# S7_RF.net
KiCad netlist of a schematic drawn in Altium Designer
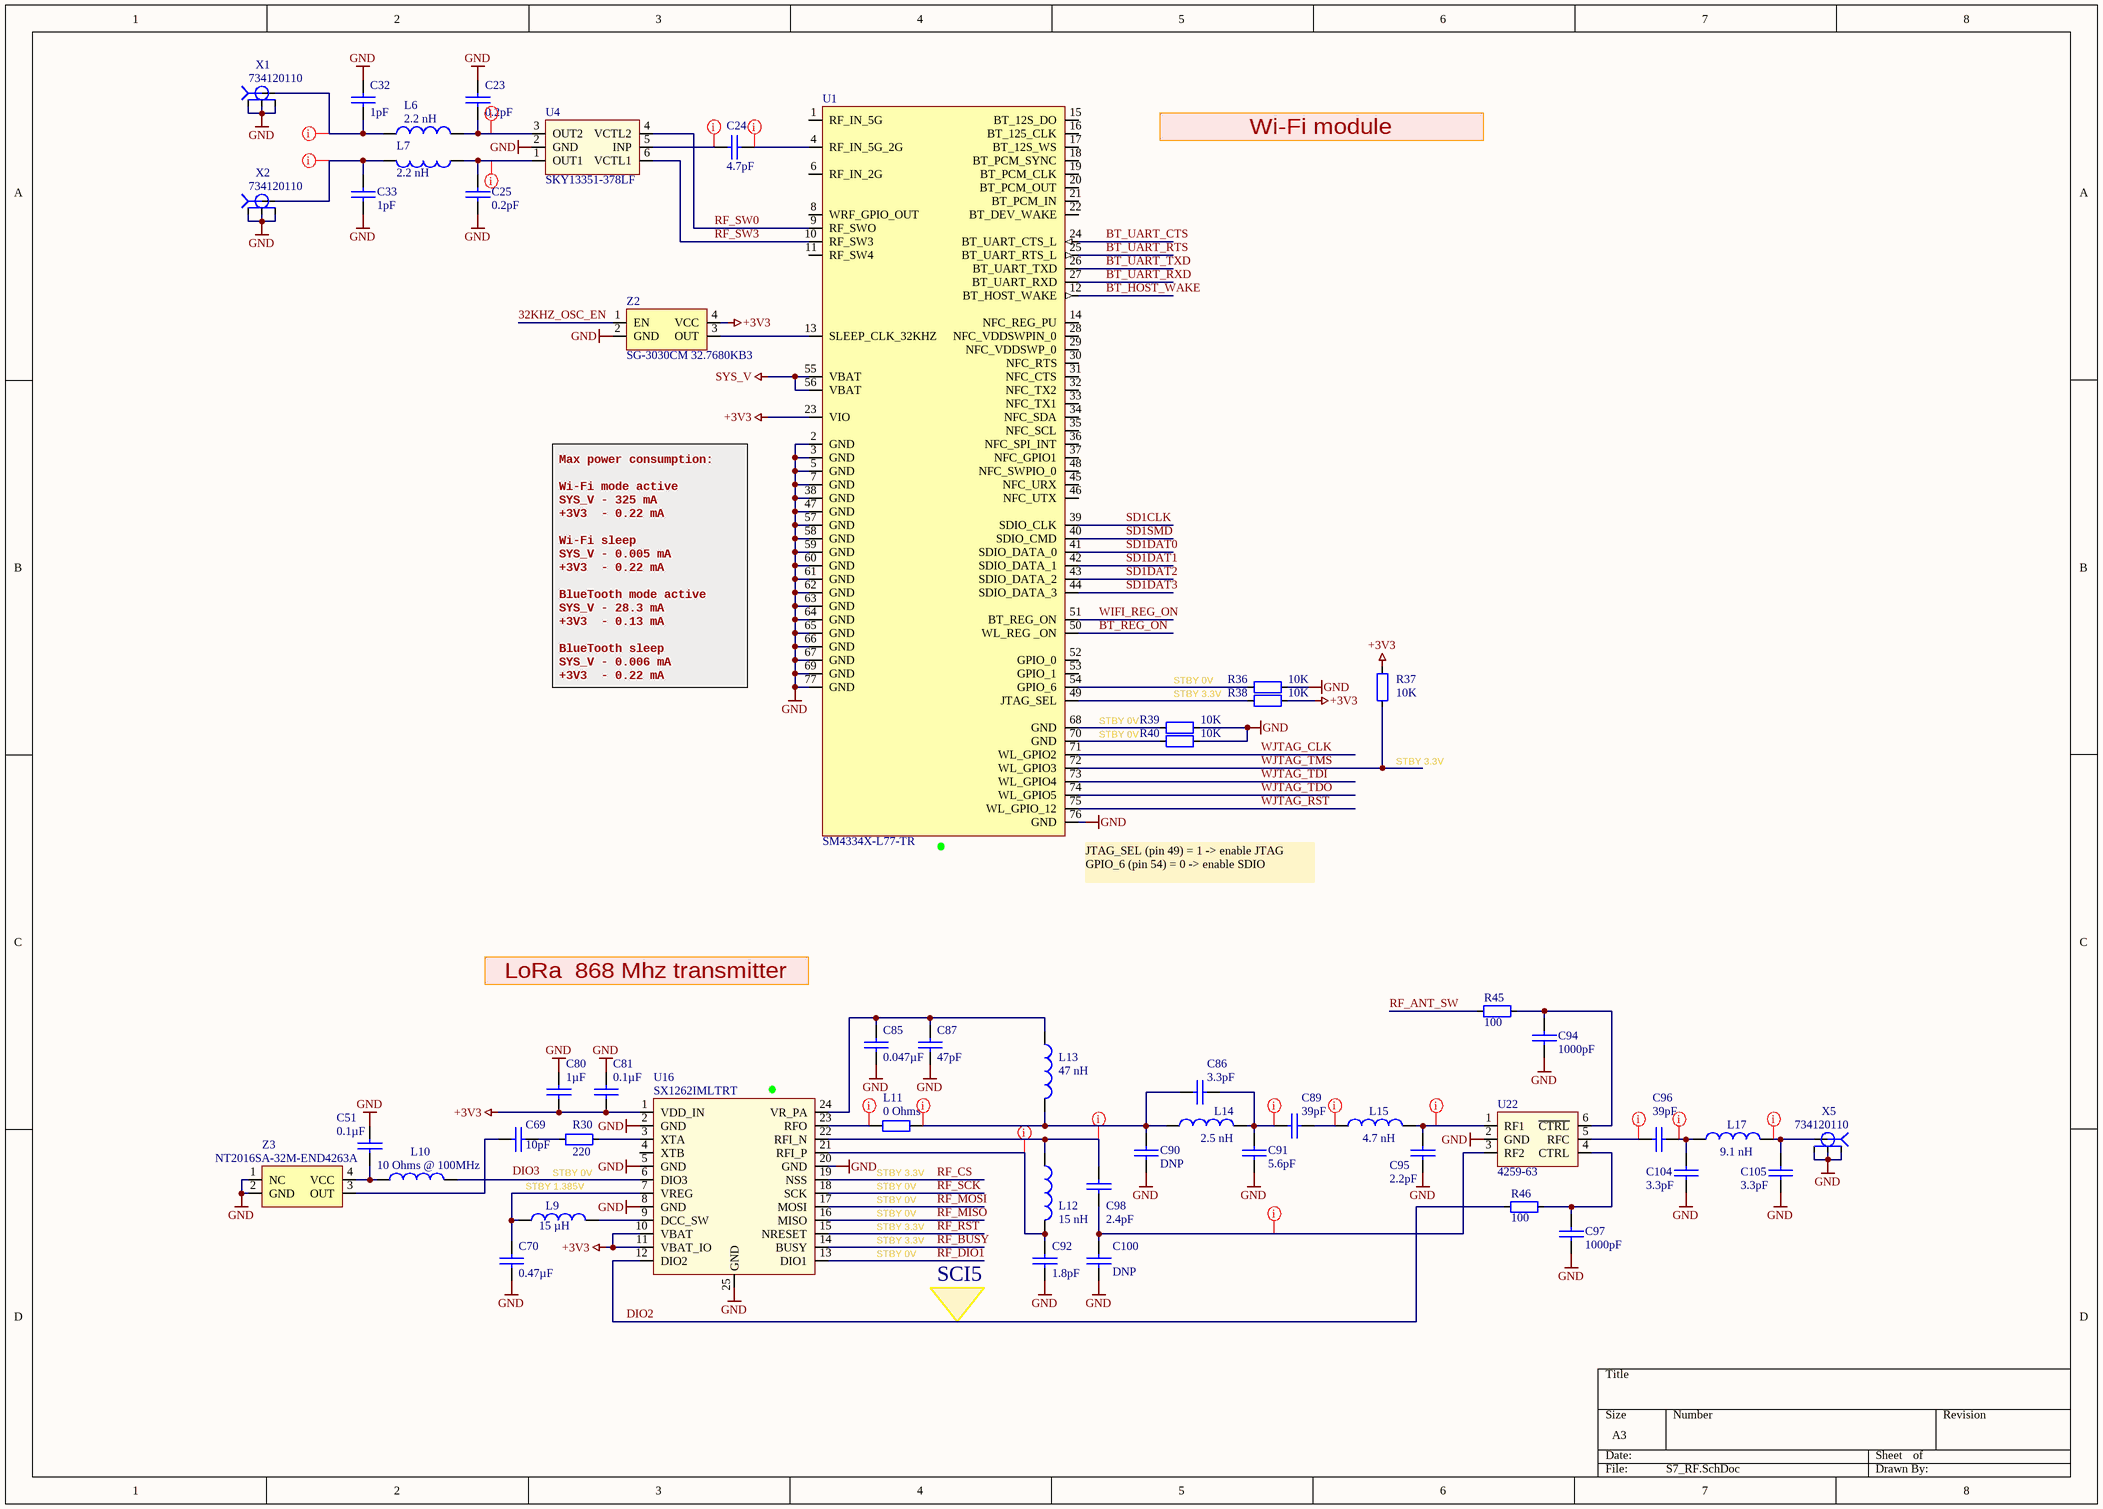
[diagram p0: S7_RF.SchDoc]

(export (version "E")
  (design (tool "Eeschema 10.0.6"))
  (components
    (comp (ref "C23")
      (value "0.2pF")
      (footprint "0402 CAP")
      (fields
        (field (name "PART NUMBER") "500R07S0R2BV4T")
        (field (name "MANUFACTURER") "Johanson Technology Inc.")
        (field (name "PARTNUM") "712-1160-1-ND")
      )
      (libsource (lib "ea_PassivComps") (part "Capacitor"))
    )
    (comp (ref "C24")
      (value "4.7pF")
      (footprint "0402 CAP")
      (fields
        (field (name "PART NUMBER") "500R07S4R7CV4T")
        (field (name "MANUFACTURER") "Johanson Technology Inc.")
        (field (name "PARTNUM") "712-1287-1-ND")
      )
      (libsource (lib "ea_PassivComps") (part "Capacitor"))
    )
    (comp (ref "C25")
      (value "0.2pF")
      (footprint "0402 CAP")
      (fields
        (field (name "PART NUMBER") "500R07S0R2BV4T")
        (field (name "MANUFACTURER") "Johanson Technology Inc.")
        (field (name "PARTNUM") "712-1160-1-ND")
      )
      (libsource (lib "ea_PassivComps") (part "Capacitor"))
    )
    (comp (ref "C32")
      (value "1pF")
      (footprint "0402 CAP")
      (fields
        (field (name "PART NUMBER") "GJM1555C1H1R0CB01D")
        (field (name "MANUFACTURER") "Murata Electronics North America")
        (field (name "PARTNUM") "490-3083-1-ND")
      )
      (libsource (lib "ea_PassivComps") (part "Capacitor"))
    )
    (comp (ref "C33")
      (value "1pF")
      (footprint "0402 CAP")
      (fields
        (field (name "PART NUMBER") "GJM1555C1H1R0CB01D")
        (field (name "MANUFACTURER") "Murata Electronics North America")
        (field (name "PARTNUM") "490-3083-1-ND")
      )
      (libsource (lib "ea_PassivComps") (part "Capacitor"))
    )
    (comp (ref "C51")
      (value "0.1µF")
      (footprint "0402 CAP")
      (description "0.1µF, ±10%, 50V, X7R, 0402 (1005 Metric), -55°C ~ 125°C, -, General Purpose")
      (fields
        (field (name "PART NUMBER") "0402B104K500CT")
        (field (name "MANUFACTURER") "Walsin Technology Corporation")
      )
      (libsource (lib "ea_PassivComps") (part "Capacitor"))
    )
    (comp (ref "C69")
      (value "10pF")
      (footprint "0402 CAP")
      (fields
        (field (name "PART NUMBER") "GJM1555C1H100FB01D")
        (field (name "MANUFACTURER") "Murata Electronics North America")
        (field (name "PARTNUM") "490-11189-1-ND")
      )
      (libsource (lib "ea_PassivComps") (part "Capacitor"))
    )
    (comp (ref "C70")
      (value "0.47µF")
      (footprint "0402 CAP")
      (description "0.47µF, ±20%, 25V, X5R, 0402 (1005 Metric), -55°C ~ 85°C, -, Automotive")
      (fields
        (field (name "PART NUMBER") "GRT155R61E474ME01D")
        (field (name "MANUFACTURER") "Murata Electronics North America")
      )
      (libsource (lib "ea_PassivComps") (part "Capacitor"))
    )
    (comp (ref "C80")
      (value "1µF")
      (footprint "0402 CAP")
      (description "1µF, ±20%, 25V, X5R, 0402 (1005 Metric), -55°C ~ 85°C, -, General Purpose")
      (fields (field (name "PART NUMBER") "TMK105BJ105MV-F") (field (name "MANUFACTURER") "Taiyo Yuden"))
      (libsource (lib "ea_PassivComps") (part "Capacitor"))
    )
    (comp (ref "C81")
      (value "0.1µF")
      (footprint "0402 CAP")
      (description "0.1µF, ±10%, 50V, X7R, 0402 (1005 Metric), -55°C ~ 125°C, -, General Purpose")
      (fields
        (field (name "PART NUMBER") "0402B104K500CT")
        (field (name "MANUFACTURER") "Walsin Technology Corporation")
      )
      (libsource (lib "ea_PassivComps") (part "Capacitor"))
    )
    (comp (ref "C85")
      (value "0.047µF")
      (footprint "0402 CAP")
      (description "0.047µF, ±10%, 25V, X7R, 0402 (1005 Metric), -55°C ~ 125°C, -, General Purpose")
      (fields (field (name "PART NUMBER") "CC0402KRX7R8BB473") (field (name "MANUFACTURER") "Yageo"))
      (libsource (lib "ea_PassivComps") (part "Capacitor"))
    )
    (comp (ref "C86")
      (value "3.3pF")
      (footprint "0402 CAP")
      (description "3.3pF, ±0.1pF, 50V, C0G, NP0, 0402 (1005 Metric), -55°C ~ 125°C, -, RF, Microwave, High Frequency")
      (fields
        (field (name "PART NUMBER") "885392005011")
        (field (name "MANUFACTURER") "Wurth Electronics Inc.")
      )
      (libsource (lib "ea_PassivComps") (part "Capacitor"))
    )
    (comp (ref "C87")
      (value "47pF")
      (footprint "0402 CAP")
      (fields
        (field (name "PART NUMBER") "GJM1555C1H470FB01D")
        (field (name "MANUFACTURER") "Murata Electronics North America")
        (field (name "PARTNUM") "490-16376-1-ND")
      )
      (libsource (lib "ea_PassivComps") (part "Capacitor"))
    )
    (comp (ref "C89")
      (value "39pF")
      (footprint "0402 CAP")
      (fields
        (field (name "PART NUMBER") "GJM1555C1H390JB01D")
        (field (name "MANUFACTURER") "Murata Electronics North America")
        (field (name "PARTNUM") "490-17673-1-ND")
      )
      (libsource (lib "ea_PassivComps") (part "Capacitor"))
    )
    (comp (ref "C90")
      (value "DNP")
      (footprint "0402 CAP")
      (fields (field (name "Comment") "Capacitor_0402"))
      (libsource (lib "ea_Capacitors") (part "Capacitor_0402"))
    )
    (comp (ref "C91")
      (value "5.6pF")
      (footprint "0402 CAP")
      (fields
        (field (name "PART NUMBER") "GJM1555C1H5R6BB01D")
        (field (name "MANUFACTURER") "Murata Electronics North America")
        (field (name "PARTNUM") "490-11225-1-ND")
      )
      (libsource (lib "ea_PassivComps") (part "Capacitor"))
    )
    (comp (ref "C92")
      (value "1.8pF")
      (footprint "0402 CAP")
      (fields
        (field (name "PART NUMBER") "GJM1555C1H1R8BB01D")
        (field (name "MANUFACTURER") "Murata Electronics North America")
        (field (name "PARTNUM") "490-8089-1-ND")
      )
      (libsource (lib "ea_PassivComps") (part "Capacitor"))
    )
    (comp (ref "C94")
      (value "1000pF")
      (footprint "0402 CAP")
      (description "1000pF, ±5%, 50V, CH, 0402 (1005 Metric), -25°C ~ 85°C, Low ESL, General Purpose")
      (fields
        (field (name "PART NUMBER") "C1005CH1H102J050BA")
        (field (name "MANUFACTURER") "TDK Corporation")
      )
      (libsource (lib "ea_PassivComps") (part "Capacitor"))
    )
    (comp (ref "C95")
      (value "2.2pF")
      (footprint "0402 CAP")
      (fields
        (field (name "PART NUMBER") "CBR04C229B5GAC")
        (field (name "MANUFACTURER") "KEMET")
        (field (name "PARTNUM") "399-17527-1-ND")
      )
      (libsource (lib "ea_PassivComps") (part "Capacitor"))
    )
    (comp (ref "C96")
      (value "39pF")
      (footprint "0402 CAP")
      (fields
        (field (name "PART NUMBER") "GJM1555C1H390JB01D")
        (field (name "MANUFACTURER") "Murata Electronics North America")
        (field (name "PARTNUM") "490-17673-1-ND")
      )
      (libsource (lib "ea_PassivComps") (part "Capacitor"))
    )
    (comp (ref "C97")
      (value "1000pF")
      (footprint "0402 CAP")
      (description "1000pF, ±5%, 50V, CH, 0402 (1005 Metric), -25°C ~ 85°C, Low ESL, General Purpose")
      (fields
        (field (name "PART NUMBER") "C1005CH1H102J050BA")
        (field (name "MANUFACTURER") "TDK Corporation")
      )
      (libsource (lib "ea_PassivComps") (part "Capacitor"))
    )
    (comp (ref "C98")
      (value "2.4pF")
      (footprint "0402 CAP")
      (fields
        (field (name "PART NUMBER") "GJM1555C1H2R4BB01D")
        (field (name "MANUFACTURER") "Murata Electronics North America")
        (field (name "PARTNUM") "490-8093-1-ND")
      )
      (libsource (lib "ea_PassivComps") (part "Capacitor"))
    )
    (comp (ref "C100")
      (value "DNP")
      (footprint "0402 CAP")
      (fields (field (name "Comment") "Capacitor_0402"))
      (libsource (lib "ea_Capacitors") (part "Capacitor_0402"))
    )
    (comp (ref "C104")
      (value "3.3pF")
      (footprint "0402 CAP")
      (description "3.3pF, ±0.1pF, 50V, C0G, NP0, 0402 (1005 Metric), -55°C ~ 125°C, -, RF, Microwave, High Frequency")
      (fields
        (field (name "PART NUMBER") "885392005011")
        (field (name "MANUFACTURER") "Wurth Electronics Inc.")
      )
      (libsource (lib "ea_PassivComps") (part "Capacitor"))
    )
    (comp (ref "C105")
      (value "3.3pF")
      (footprint "0402 CAP")
      (description "3.3pF, ±0.1pF, 50V, C0G, NP0, 0402 (1005 Metric), -55°C ~ 125°C, -, RF, Microwave, High Frequency")
      (fields
        (field (name "PART NUMBER") "885392005011")
        (field (name "MANUFACTURER") "Wurth Electronics Inc.")
      )
      (libsource (lib "ea_PassivComps") (part "Capacitor"))
    )
    (comp (ref "L6")
      (value "2.2 nH")
      (footprint "INDC1005-0402")
      (description "2.2nH ±0.1nH, Q=13 @ 500MHz, 6GHz, Inductor 220mA 300 mOhm Max, -40°C ~ 85°C, 0402")
      (fields
        (field (name "MANUFACTURER") "Murata Electronics North America")
        (field (name "TOLERANCE") "±0.1nH")
      )
      (libsource (lib "") (part "LQP15MN2N2B02D_1"))
    )
    (comp (ref "L7")
      (value "2.2 nH")
      (footprint "INDC1005-0402")
      (description "2.2nH ±0.1nH, Q=13 @ 500MHz, 6GHz, Inductor 220mA 300 mOhm Max, -40°C ~ 85°C, 0402")
      (fields
        (field (name "MANUFACTURER") "Murata Electronics North America")
        (field (name "TOLERANCE") "±0.1nH")
      )
      (libsource (lib "ea_RF_inductors") (part "LQP15MN2N2B02D"))
    )
    (comp (ref "L9")
      (value "15 µH")
      (footprint "2012[0805]")
      (description "15µH Shielded Multilayer Inductor 250mA 950 mOhm 0805 (2012 Metric)")
      (fields (field (name "MANUFACTURER") "TDK Corporation") (field (name "PARTNUM") "445-6397-1-ND"))
      (libsource (lib "ea_RF_inductors") (part "MLZ2012M150WT000"))
    )
    (comp (ref "L10")
      (value "10 Ohms @ 100MHz")
      (footprint "INDC1005-0402")
      (description "10 Ohms @ 100MHz 1 Power Line Ferrite Bead 0402 (1005 Metric) 1A 25 mOhm")
      (fields
        (field (name "MANUFACTURER") "Murata Electronics North America")
        (field (name "PARTNUM") "490-5976-1-ND")
      )
      (libsource (lib "ea_RF_inductors") (part "BLM15PG100SN1D"))
    )
    (comp (ref "L11")
      (value "0 Ohms")
      (footprint "INDC1005-0402")
      (description "0 Ohms Jumper 0.063W, 1/16W Chip Resistor 0402 (1005 Metric) Automotive AEC-Q200 Thick Film")
      (fields (field (name "MANUFACTURER") "Vishay Dale") (field (name "PARTNUM") "541-0.0JCT-ND"))
      (libsource (lib "ea_RF_inductors") (part "CRCW04020000Z0ED"))
    )
    (comp (ref "L12")
      (value "15 nH")
      (footprint "INDC1005-0402")
      (description "15nH Unshielded Wirewound Inductor 460mA 160 mOhm Max 0402 (1006 Metric)")
      (fields (field (name "MANUFACTURER") "Murata") (field (name "TOLERANCE") "±3%"))
      (libsource (lib "ea_RF_inductors") (part "LQW15AN15NH00D"))
    )
    (comp (ref "L13")
      (value "47 nH")
      (footprint "INDC1005-0402")
      (description "47nH Unshielded Wirewound Inductor 210mA 1.08 Ohm Max 0402 (1005 Metric)")
      (fields (field (name "MANUFACTURER") "Murata") (field (name "TOLERANCE") "±5%"))
      (libsource (lib "ea_RF_inductors") (part "LQW15AN47NJ00D"))
    )
    (comp (ref "L14")
      (value "2.5 nH")
      (footprint "INDC1005-0402")
      (description "2.5nH Unshielded Wirewound Inductor 850mA 50 mOhm Max 0402 (1006 Metric)")
      (fields (field (name "MANUFACTURER") "Murata") (field (name "TOLERANCE") "±0.2nH"))
      (libsource (lib "ea_RF_inductors") (part "LQW15AN2N5C00D"))
    )
    (comp (ref "L15")
      (value "4.7 nH")
      (footprint "INDC1005-0402")
      (description "4.7nH Unshielded Wirewound Inductor 750mA 70 mOhm Max 0402 (1006 Metric)")
      (fields
        (field (name "MANUFACTURER") "Murata Electronics North America")
        (field (name "TOLERANCE") "±0.2nH")
      )
      (libsource (lib "ea_RF_inductors") (part "LQW15AN4N7C00D"))
    )
    (comp (ref "L17")
      (value "9.1 nH")
      (footprint "INDC1005-0402")
      (description "9.1nH Unshielded Wirewound Inductor 540mA 140 mOhm Max 0402 (1006 Metric)")
      (fields
        (field (name "MANUFACTURER") "Murata Electronics North America")
        (field (name "TOLERANCE") "±3%")
      )
      (libsource (lib "ea_RF_inductors") (part "LQW15AN9N1H00D"))
    )
    (comp (ref "R30")
      (value "220")
      (footprint "0402")
      (fields
        (field (name "MANUFACTURER") "Yageo")
        (field (name "TOLERANCE") "±1%")
        (field (name "VOLTAGE") "75V")
      )
      (libsource (lib "") (part "Resistor_1"))
    )
    (comp (ref "R36")
      (value "10K")
      (footprint "0402")
      (description "10 K, 0402, Thick Film, -55..+155")
      (fields (field (name "MANUFACTURER") "Rohm Semiconductor") (field (name "TOLERANCE") "5%"))
      (libsource (lib "ea_Resistors") (part "MCR01MZPJ103"))
    )
    (comp (ref "R37")
      (value "10K")
      (footprint "0402")
      (description "10 K, 0402, Thick Film, -55..+155")
      (fields (field (name "MANUFACTURER") "Rohm Semiconductor") (field (name "TOLERANCE") "5%"))
      (libsource (lib "") (part "MCR01MZPJ103_1"))
    )
    (comp (ref "R38")
      (value "10K")
      (footprint "0402")
      (description "10 K, 0402, Thick Film, -55..+155")
      (fields (field (name "MANUFACTURER") "Rohm Semiconductor") (field (name "TOLERANCE") "5%"))
      (libsource (lib "ea_Resistors") (part "MCR01MZPJ103"))
    )
    (comp (ref "R39")
      (value "10K")
      (footprint "0402")
      (description "10 K, 0402, Thick Film, -55..+155")
      (fields (field (name "MANUFACTURER") "Rohm Semiconductor") (field (name "TOLERANCE") "5%"))
      (libsource (lib "ea_Resistors") (part "MCR01MZPJ103"))
    )
    (comp (ref "R40")
      (value "10K")
      (footprint "0402")
      (description "10 K, 0402, Thick Film, -55..+155")
      (fields (field (name "MANUFACTURER") "Rohm Semiconductor") (field (name "TOLERANCE") "5%"))
      (libsource (lib "ea_Resistors") (part "MCR01MZPJ103"))
    )
    (comp (ref "R45")
      (value "100")
      (footprint "0402")
      (fields
        (field (name "MANUFACTURER") "Stackpole Electronics Inc")
        (field (name "TOLERANCE") "±1%")
        (field (name "VOLTAGE") "75V")
      )
      (libsource (lib "ea_PassivComps") (part "Resistor"))
    )
    (comp (ref "R46")
      (value "100")
      (footprint "0402")
      (fields
        (field (name "MANUFACTURER") "Stackpole Electronics Inc")
        (field (name "TOLERANCE") "±1%")
        (field (name "VOLTAGE") "75V")
      )
      (libsource (lib "ea_PassivComps") (part "Resistor"))
    )
    (comp (ref "U1")
      (value "SM4334X-L77-TR")
      (footprint "ISM43340-L77-TR")
      (fields (field (name "PARTNUM") "1475-1047-1-ND"))
      (libsource (lib "ea_WiFi_modules") (part "SM4334X-L77-TR"))
    )
    (comp (ref "U4")
      (value "SKY13351-378LF")
      (footprint "SKY13351-378LF")
      (description "RF Switch IC 802.11/WiFi, WLAN SPDT 6GHz 50 Ohm, -40°C ~ 85°C, 6-MLPD (1x1)")
      (fields
        (field (name "MANUFACTURER") "Skyworks Solutions Inc.")
        (field (name "PARTNUM") "863-1177-1-ND")
      )
      (libsource (lib "ea_IC_RF") (part "SKY13351-378LF"))
    )
    (comp (ref "U16")
      (value "SX1262IMLTRT")
      (footprint "VQFN24")
      (description "IC RF TxRx Only General ISM < 1GHz LoRaWAN 150MHz ~ 960MHz 24-VFQFN Exposed Pad")
      (fields (field (name "MANUFACTURER") "Semtech Corporation"))
      (libsource (lib "ea_IC_RF") (part "SX1262IMLTRT"))
    )
    (comp (ref "U22")
      (value "4196")
      (footprint "SC70-6")
      (description "RF Switch IC General Purpose SPDT 3GHz 50 Ohm SC-70-6")
      (fields
        (field (name "MANUFACTURER") "pSemi")
        (field (name "PARTNUM") "1046-1011-2-ND")
        (field (name "PARTNAME") "4259-63")
      )
      (libsource (lib "ea_IC_RF") (part "4259-63"))
    )
    (comp (ref "X1")
      (value "734120110")
      (footprint "0734120110")
      (description "U.FL (UMCC) Connector Receptacle, Male Pin 50 Ohm Surface Mount Solder")
      (fields (field (name "MANUFACTURER") "Molex") (field (name "PARTNUM") "WM5587TR-ND"))
      (libsource (lib "ea_Connectors_RF") (part "0734120110"))
    )
    (comp (ref "X2")
      (value "734120110")
      (footprint "0734120110")
      (description "U.FL (UMCC) Connector Receptacle, Male Pin 50 Ohm Surface Mount Solder")
      (fields (field (name "MANUFACTURER") "Molex") (field (name "PARTNUM") "WM5587TR-ND"))
      (libsource (lib "ea_Connectors_RF") (part "0734120110"))
    )
    (comp (ref "X5")
      (value "734120110")
      (footprint "0734120110")
      (description "U.FL (UMCC) Connector Receptacle, Male Pin 50 Ohm Surface Mount Solder")
      (fields (field (name "MANUFACTURER") "Molex") (field (name "PARTNUM") "WM5587TR-ND"))
      (libsource (lib "ea_Connectors_RF") (part "0734120110"))
    )
    (comp (ref "Z2")
      (value "SG-3030CM 32.7680KB3")
      (footprint "SG-3030CM")
      (description "32.768kHz XO (Standard) CMOS Oscillator 1.5V ~ 5.5V, -20°C ~ 70°C, 4-SMD  (3.20mm x 1.50mm)")
      (fields (field (name "MANUFACTURER") "EPSON") (field (name "PARTNUM") "SER4328CT-ND"))
      (libsource (lib "ea_OSC_CLK_GEN") (part "SG-3030CM 32.7680KB3"))
    )
    (comp (ref "Z3")
      (value "NT2016SA-32M-END4263A")
      (footprint "4-SMD 2.00mm x 1.60mm")
      (description "32MHz VCTCXO Oscillator 1.8V 4-SMD, No Lead")
      (fields (field (name "MANUFACTURER") "NDK America, Inc.") (field (name "PARTNUM") "644-1328-1-ND"))
      (libsource (lib "ea_OSC_CLK_GEN") (part "NT2016SA-32M-END4263A"))
    )
  )
  (nets
    (net (code "1") (name "+3V3") (class "Default")
      (node (ref "C80") (pin "2") (pinfunction "2_2") (pintype "passive"))
      (node (ref "C81") (pin "2") (pinfunction "2_2") (pintype "passive"))
      (node (ref "R37") (pin "2") (pinfunction "2_2") (pintype "passive"))
      (node (ref "R38") (pin "1") (pinfunction "1_1") (pintype "passive"))
      (node (ref "U1") (pin "23") (pinfunction "VIO_23") (pintype "passive"))
      (node (ref "U16") (pin "1") (pinfunction "VDD_IN_1") (pintype "power_in"))
      (node (ref "U16") (pin "10") (pinfunction "VBAT_10") (pintype "power_in"))
      (node (ref "U16") (pin "11") (pinfunction "VBAT_IO_11") (pintype "power_in"))
      (node (ref "Z2") (pin "4") (pinfunction "VCC_4") (pintype "passive"))
    )
    (net (code "2") (name "/32KHZ_OSC_EN") (class "Default")
      (node (ref "Z2") (pin "1") (pinfunction "EN_1") (pintype "passive"))
    )
    (net (code "3") (name "/BT_HOST_WAKE") (class "Default")
      (node (ref "U1") (pin "12") (pinfunction "BT_HOST_WAKE_12") (pintype "output"))
    )
    (net (code "4") (name "/BT_REG_ON") (class "Default")
      (node (ref "U1") (pin "50") (pinfunction "WL_REG__ON_50") (pintype "passive"))
    )
    (net (code "5") (name "/BT_UART_CTS") (class "Default")
      (node (ref "U1") (pin "24") (pinfunction "BT_UART_CTS_L_24") (pintype "input"))
    )
    (net (code "6") (name "/BT_UART_RTS") (class "Default")
      (node (ref "U1") (pin "25") (pinfunction "BT_UART_RTS_L_25") (pintype "output"))
    )
    (net (code "7") (name "/BT_UART_RXD") (class "Default")
      (node (ref "U1") (pin "27") (pinfunction "BT_UART_RXD_27") (pintype "bidirectional"))
    )
    (net (code "8") (name "/BT_UART_TXD") (class "Default")
      (node (ref "U1") (pin "26") (pinfunction "BT_UART_TXD_26") (pintype "bidirectional"))
    )
    (net (code "9") (name "/DIO2") (class "Default")
      (node (ref "R46") (pin "2") (pinfunction "2_2") (pintype "passive"))
      (node (ref "U16") (pin "12") (pinfunction "DIO2_12") (pintype "passive"))
    )
    (net (code "11") (name "/RF_ANT_SW") (class "Default")
      (node (ref "R45") (pin "2") (pinfunction "2_2") (pintype "passive"))
    )
    (net (code "12") (name "/RF_BUSY") (class "Default")
      (node (ref "U16") (pin "14") (pinfunction "BUSY_14") (pintype "passive"))
    )
    (net (code "13") (name "/RF_CS") (class "Default")
      (node (ref "U16") (pin "19") (pinfunction "NSS_19") (pintype "passive"))
    )
    (net (code "14") (name "/RF_DIO1") (class "Default")
      (node (ref "U16") (pin "13") (pinfunction "DIO1_13") (pintype "passive"))
    )
    (net (code "15") (name "/RF_MISO") (class "Default")
      (node (ref "U16") (pin "16") (pinfunction "MISO_16") (pintype "passive"))
    )
    (net (code "16") (name "/RF_MOSI") (class "Default")
      (node (ref "U16") (pin "17") (pinfunction "MOSI_17") (pintype "passive"))
    )
    (net (code "17") (name "/RF_RST") (class "Default")
      (node (ref "U16") (pin "15") (pinfunction "NRESET_15") (pintype "passive"))
    )
    (net (code "18") (name "/RF_SCK") (class "Default")
      (node (ref "U16") (pin "18") (pinfunction "SCK_18") (pintype "passive"))
    )
    (net (code "19") (name "/RF_SW0") (class "Default")
      (node (ref "U1") (pin "9") (pinfunction "RF_SWO_9") (pintype "passive"))
      (node (ref "U4") (pin "4") (pinfunction "VCTL2_4") (pintype "passive"))
    )
    (net (code "20") (name "/RF_SW3") (class "Default")
      (node (ref "U1") (pin "10") (pinfunction "RF_SW3_10") (pintype "passive"))
      (node (ref "U4") (pin "6") (pinfunction "VCTL1_6") (pintype "passive"))
    )
    (net (code "21") (name "/SD1CLK") (class "Default")
      (node (ref "U1") (pin "39") (pinfunction "SDIO_CLK_39") (pintype "passive"))
    )
    (net (code "22") (name "/SD1DAT0") (class "Default")
      (node (ref "U1") (pin "41") (pinfunction "SDIO_DATA_0_41") (pintype "bidirectional"))
    )
    (net (code "23") (name "/SD1DAT1") (class "Default")
      (node (ref "U1") (pin "42") (pinfunction "SDIO_DATA_1_42") (pintype "bidirectional"))
    )
    (net (code "24") (name "/SD1DAT2") (class "Default")
      (node (ref "U1") (pin "43") (pinfunction "SDIO_DATA_2_43") (pintype "bidirectional"))
    )
    (net (code "25") (name "/SD1DAT3") (class "Default")
      (node (ref "U1") (pin "44") (pinfunction "SDIO_DATA_3_44") (pintype "bidirectional"))
    )
    (net (code "26") (name "/SD1SMD") (class "Default")
      (node (ref "U1") (pin "40") (pinfunction "SDIO_CMD_40") (pintype "bidirectional"))
    )
    (net (code "27") (name "/WIFI_REG_ON") (class "Default")
      (node (ref "U1") (pin "51") (pinfunction "BT_REG_ON_51") (pintype "passive"))
    )
    (net (code "28") (name "/WJTAG_CLK") (class "Default")
      (node (ref "U1") (pin "71") (pinfunction "WL_GPIO2_71") (pintype "bidirectional"))
    )
    (net (code "29") (name "/WJTAG_RST") (class "Default")
      (node (ref "U1") (pin "75") (pinfunction "WL_GPIO_12_75") (pintype "bidirectional"))
    )
    (net (code "30") (name "/WJTAG_TDI") (class "Default")
      (node (ref "U1") (pin "73") (pinfunction "WL_GPIO4_73") (pintype "bidirectional"))
    )
    (net (code "31") (name "/WJTAG_TDO") (class "Default")
      (node (ref "U1") (pin "74") (pinfunction "WL_GPIO5_74") (pintype "bidirectional"))
    )
    (net (code "32") (name "/WJTAG_TMS") (class "Default")
      (node (ref "R37") (pin "1") (pinfunction "1_1") (pintype "passive"))
      (node (ref "U1") (pin "72") (pinfunction "WL_GPIO3_72") (pintype "bidirectional"))
    )
    (net (code "33") (name "GND") (class "Default")
      (node (ref "C100") (pin "2") (pinfunction "2_2") (pintype "passive"))
      (node (ref "C104") (pin "1") (pinfunction "1_1") (pintype "passive"))
      (node (ref "C105") (pin "1") (pinfunction "1_1") (pintype "passive"))
      (node (ref "C23") (pin "1") (pinfunction "1_1") (pintype "passive"))
      (node (ref "C25") (pin "1") (pinfunction "1_1") (pintype "passive"))
      (node (ref "C32") (pin "1") (pinfunction "1_1") (pintype "passive"))
      (node (ref "C33") (pin "1") (pinfunction "1_1") (pintype "passive"))
      (node (ref "C51") (pin "1") (pinfunction "1_1") (pintype "passive"))
      (node (ref "C70") (pin "2") (pinfunction "2_2") (pintype "passive"))
      (node (ref "C80") (pin "1") (pinfunction "1_1") (pintype "passive"))
      (node (ref "C81") (pin "1") (pinfunction "1_1") (pintype "passive"))
      (node (ref "C85") (pin "2") (pinfunction "2_2") (pintype "passive"))
      (node (ref "C87") (pin "2") (pinfunction "2_2") (pintype "passive"))
      (node (ref "C90") (pin "2") (pinfunction "2_2") (pintype "passive"))
      (node (ref "C91") (pin "2") (pinfunction "2_2") (pintype "passive"))
      (node (ref "C92") (pin "2") (pinfunction "2_2") (pintype "passive"))
      (node (ref "C94") (pin "1") (pinfunction "1_1") (pintype "passive"))
      (node (ref "C95") (pin "2") (pinfunction "2_2") (pintype "passive"))
      (node (ref "C97") (pin "1") (pinfunction "1_1") (pintype "passive"))
      (node (ref "R36") (pin "1") (pinfunction "1_1") (pintype "passive"))
      (node (ref "R39") (pin "1") (pinfunction "1_1") (pintype "passive"))
      (node (ref "R40") (pin "1") (pinfunction "1_1") (pintype "passive"))
      (node (ref "U1") (pin "2") (pinfunction "GND_2") (pintype "passive"))
      (node (ref "U1") (pin "3") (pinfunction "GND_3") (pintype "passive"))
      (node (ref "U1") (pin "38") (pinfunction "GND_38") (pintype "passive"))
      (node (ref "U1") (pin "47") (pinfunction "GND_47") (pintype "passive"))
      (node (ref "U1") (pin "5") (pinfunction "GND_5") (pintype "passive"))
      (node (ref "U1") (pin "57") (pinfunction "GND_57") (pintype "passive"))
      (node (ref "U1") (pin "58") (pinfunction "GND_58") (pintype "passive"))
      (node (ref "U1") (pin "59") (pinfunction "GND_59") (pintype "passive"))
      (node (ref "U1") (pin "60") (pinfunction "GND_60") (pintype "passive"))
      (node (ref "U1") (pin "61") (pinfunction "GND_61") (pintype "passive"))
      (node (ref "U1") (pin "62") (pinfunction "GND_62") (pintype "passive"))
      (node (ref "U1") (pin "63") (pinfunction "GND_63") (pintype "passive"))
      (node (ref "U1") (pin "64") (pinfunction "GND_64") (pintype "passive"))
      (node (ref "U1") (pin "65") (pinfunction "GND_65") (pintype "passive"))
      (node (ref "U1") (pin "66") (pinfunction "GND_66") (pintype "passive"))
      (node (ref "U1") (pin "67") (pinfunction "GND_67") (pintype "passive"))
      (node (ref "U1") (pin "69") (pinfunction "GND_69") (pintype "passive"))
      (node (ref "U1") (pin "7") (pinfunction "GND_7") (pintype "passive"))
      (node (ref "U1") (pin "76") (pinfunction "GND_76") (pintype "passive"))
      (node (ref "U1") (pin "77") (pinfunction "GND_77") (pintype "passive"))
      (node (ref "U16") (pin "2") (pinfunction "GND_2") (pintype "passive"))
      (node (ref "U16") (pin "20") (pinfunction "GND_20") (pintype "passive"))
      (node (ref "U16") (pin "25") (pinfunction "GND_25") (pintype "passive"))
      (node (ref "U16") (pin "5") (pinfunction "GND_5") (pintype "passive"))
      (node (ref "U16") (pin "8") (pinfunction "GND_8") (pintype "passive"))
      (node (ref "U22") (pin "2") (pinfunction "GND_2") (pintype "passive"))
      (node (ref "U4") (pin "2") (pinfunction "GND_2") (pintype "passive"))
      (node (ref "X1") (pin "2") (pinfunction "2_2") (pintype "passive"))
      (node (ref "X1") (pin "3") (pinfunction "3_3") (pintype "passive"))
      (node (ref "X1") (pin "4") (pinfunction "3_4") (pintype "passive"))
      (node (ref "X2") (pin "2") (pinfunction "2_2") (pintype "passive"))
      (node (ref "X2") (pin "3") (pinfunction "3_3") (pintype "passive"))
      (node (ref "X2") (pin "4") (pinfunction "3_4") (pintype "passive"))
      (node (ref "X5") (pin "2") (pinfunction "2_2") (pintype "passive"))
      (node (ref "X5") (pin "3") (pinfunction "3_3") (pintype "passive"))
      (node (ref "X5") (pin "4") (pinfunction "3_4") (pintype "passive"))
      (node (ref "Z2") (pin "2") (pinfunction "GND_2") (pintype "passive"))
      (node (ref "Z3") (pin "1") (pinfunction "NC_1") (pintype "passive"))
      (node (ref "Z3") (pin "2") (pinfunction "GND_2") (pintype "passive"))
    )
    (net (code "34") (name "Net-(C69-Pad2)") (class "Default")
      (node (ref "C69") (pin "2") (pinfunction "2_2") (pintype "passive"))
      (node (ref "R30") (pin "1") (pinfunction "1_1") (pintype "passive"))
    )
    (net (code "35") (name "Net-(C86-Pad1)") (class "Default")
      (node (ref "C86") (pin "1") (pinfunction "1_1") (pintype "passive"))
      (node (ref "C90") (pin "1") (pinfunction "1_1") (pintype "passive"))
      (node (ref "L11") (pin "2") (pinfunction "2_2") (pintype "passive"))
      (node (ref "L13") (pin "2") (pinfunction "2_2") (pintype "passive"))
      (node (ref "L14") (pin "1") (pinfunction "1_1") (pintype "passive"))
    )
    (net (code "36") (name "Net-(C86-Pad2)") (class "Default")
      (node (ref "C86") (pin "2") (pinfunction "2_2") (pintype "passive"))
      (node (ref "C89") (pin "1") (pinfunction "1_1") (pintype "passive"))
      (node (ref "C91") (pin "1") (pinfunction "1_1") (pintype "passive"))
      (node (ref "L14") (pin "2") (pinfunction "2_2") (pintype "passive"))
    )
    (net (code "37") (name "Net-(C89-Pad2)") (class "Default")
      (node (ref "C89") (pin "2") (pinfunction "2_2") (pintype "passive"))
      (node (ref "L15") (pin "1") (pinfunction "1_1") (pintype "passive"))
    )
    (net (code "38") (name "Net-(C104-Pad2)") (class "Default")
      (node (ref "C104") (pin "2") (pinfunction "2_2") (pintype "passive"))
      (node (ref "C96") (pin "2") (pinfunction "2_2") (pintype "passive"))
      (node (ref "L17") (pin "1") (pinfunction "1_1") (pintype "passive"))
    )
    (net (code "39") (name "Net-(R39-Pad2)") (class "Default")
      (node (ref "R39") (pin "2") (pinfunction "2_2") (pintype "passive"))
      (node (ref "U1") (pin "68") (pinfunction "GND_68") (pintype "passive"))
    )
    (net (code "40") (name "Net-(R40-Pad2)") (class "Default")
      (node (ref "R40") (pin "2") (pinfunction "2_2") (pintype "passive"))
      (node (ref "U1") (pin "70") (pinfunction "GND_70") (pintype "passive"))
    )
    (net (code "41") (name "Net-(U1-GPIO_6)") (class "Default")
      (node (ref "R36") (pin "2") (pinfunction "2_2") (pintype "passive"))
      (node (ref "U1") (pin "54") (pinfunction "GPIO_6_54") (pintype "bidirectional"))
    )
    (net (code "42") (name "Net-(U1-JTAG_SEL)") (class "Default")
      (node (ref "R38") (pin "2") (pinfunction "2_2") (pintype "passive"))
      (node (ref "U1") (pin "49") (pinfunction "JTAG_SEL_49") (pintype "passive"))
    )
    (net (code "43") (name "Net-(U1-RF_IN_5G_2G)") (class "Default")
      (node (ref "C24") (pin "2") (pinfunction "2_2") (pintype "passive"))
      (node (ref "U1") (pin "4") (pinfunction "RF_IN_5G_2G_4") (pintype "passive"))
    )
    (net (code "44") (name "Net-(U1-SLEEP_CLK_32KHZ)") (class "Default")
      (node (ref "U1") (pin "13") (pinfunction "SLEEP_CLK_32KHZ_13") (pintype "bidirectional"))
      (node (ref "Z2") (pin "3") (pinfunction "OUT_3") (pintype "passive"))
    )
    (net (code "45") (name "Net-(U4-INP)") (class "Default")
      (node (ref "C24") (pin "1") (pinfunction "1_1") (pintype "passive"))
      (node (ref "U4") (pin "5") (pinfunction "INP_5") (pintype "passive"))
    )
    (net (code "46") (name "Net-(U4-OUT1)") (class "Default")
      (node (ref "C25") (pin "2") (pinfunction "2_2") (pintype "passive"))
      (node (ref "L7") (pin "2") (pinfunction "2_2") (pintype "passive"))
      (node (ref "U4") (pin "1") (pinfunction "OUT1_1") (pintype "passive"))
    )
    (net (code "47") (name "Net-(U4-OUT2)") (class "Default")
      (node (ref "C23") (pin "2") (pinfunction "2_2") (pintype "passive"))
      (node (ref "L6") (pin "2") (pinfunction "2_2") (pintype "passive"))
      (node (ref "U4") (pin "3") (pinfunction "OUT2_3") (pintype "passive"))
    )
    (net (code "48") (name "Net-(U16-DCC_SW)") (class "Default")
      (node (ref "L9") (pin "2") (pinfunction "2_2") (pintype "passive"))
      (node (ref "U16") (pin "9") (pinfunction "DCC_SW_9") (pintype "power_in"))
    )
    (net (code "49") (name "Net-(U16-DIO3)") (class "Default")
      (node (ref "L10") (pin "2") (pinfunction "2_2") (pintype "passive"))
      (node (ref "U16") (pin "6") (pinfunction "DIO3_6") (pintype "passive"))
    )
    (net (code "50") (name "Net-(U16-RFI_N)") (class "Default")
      (node (ref "C98") (pin "1") (pinfunction "1_1") (pintype "passive"))
      (node (ref "L12") (pin "1") (pinfunction "1_1") (pintype "passive"))
      (node (ref "U16") (pin "22") (pinfunction "RFI_N_22") (pintype "passive"))
    )
    (net (code "51") (name "Net-(U16-RFI_P)") (class "Default")
      (node (ref "C92") (pin "1") (pinfunction "1_1") (pintype "passive"))
      (node (ref "L12") (pin "2") (pinfunction "2_2") (pintype "passive"))
      (node (ref "U16") (pin "21") (pinfunction "RFI_P_21") (pintype "passive"))
    )
    (net (code "52") (name "Net-(U16-RFO)") (class "Default")
      (node (ref "L11") (pin "1") (pinfunction "1_1") (pintype "passive"))
      (node (ref "U16") (pin "23") (pinfunction "RFO_23") (pintype "passive"))
    )
    (net (code "53") (name "Net-(U16-VREG)") (class "Default")
      (node (ref "C70") (pin "1") (pinfunction "1_1") (pintype "passive"))
      (node (ref "L9") (pin "1") (pinfunction "1_1") (pintype "passive"))
      (node (ref "U16") (pin "7") (pinfunction "VREG_7") (pintype "power_in"))
    )
    (net (code "54") (name "Net-(U16-VR_PA)") (class "Default")
      (node (ref "C85") (pin "1") (pinfunction "1_1") (pintype "passive"))
      (node (ref "C87") (pin "1") (pinfunction "1_1") (pintype "passive"))
      (node (ref "L13") (pin "1") (pinfunction "1_1") (pintype "passive"))
      (node (ref "U16") (pin "24") (pinfunction "VR_PA_24") (pintype "power_in"))
    )
    (net (code "55") (name "Net-(U16-XTA)") (class "Default")
      (node (ref "R30") (pin "2") (pinfunction "2_2") (pintype "passive"))
      (node (ref "U16") (pin "3") (pinfunction "XTA_3") (pintype "passive"))
    )
    (net (code "56") (name "Net-(U22-CTRL)") (class "Default")
      (node (ref "C97") (pin "2") (pinfunction "2_2") (pintype "passive"))
      (node (ref "R46") (pin "1") (pinfunction "1_1") (pintype "passive"))
      (node (ref "U22") (pin "4") (pinfunction "CTRL_4") (pintype "passive"))
    )
    (net (code "57") (name "Net-(U22-RF1)") (class "Default")
      (node (ref "C95") (pin "1") (pinfunction "1_1") (pintype "passive"))
      (node (ref "L15") (pin "2") (pinfunction "2_2") (pintype "passive"))
      (node (ref "U22") (pin "1") (pinfunction "RF1_1") (pintype "passive"))
    )
    (net (code "58") (name "Net-(U22-RF2)") (class "Default")
      (node (ref "C100") (pin "1") (pinfunction "1_1") (pintype "passive"))
      (node (ref "C98") (pin "2") (pinfunction "2_2") (pintype "passive"))
      (node (ref "U22") (pin "3") (pinfunction "RF2_3") (pintype "passive"))
    )
    (net (code "59") (name "Net-(U22-RFC)") (class "Default")
      (node (ref "C96") (pin "1") (pinfunction "1_1") (pintype "passive"))
      (node (ref "U22") (pin "5") (pinfunction "RFC_5") (pintype "passive"))
    )
    (net (code "60") (name "Net-(U22-~{CTRL})") (class "Default")
      (node (ref "C94") (pin "2") (pinfunction "2_2") (pintype "passive"))
      (node (ref "R45") (pin "1") (pinfunction "1_1") (pintype "passive"))
      (node (ref "U22") (pin "6") (pinfunction "~{CTRL}_6") (pintype "passive"))
    )
    (net (code "61") (name "Net-(X1-Sig)") (class "Default")
      (node (ref "C32") (pin "2") (pinfunction "2_2") (pintype "passive"))
      (node (ref "L6") (pin "1") (pinfunction "1_1") (pintype "passive"))
      (node (ref "X1") (pin "1") (pinfunction "Sig_1") (pintype "passive"))
    )
    (net (code "62") (name "Net-(X2-Sig)") (class "Default")
      (node (ref "C33") (pin "2") (pinfunction "2_2") (pintype "passive"))
      (node (ref "L7") (pin "1") (pinfunction "1_1") (pintype "passive"))
      (node (ref "X2") (pin "1") (pinfunction "Sig_1") (pintype "passive"))
    )
    (net (code "63") (name "Net-(X5-Sig)") (class "Default")
      (node (ref "C105") (pin "2") (pinfunction "2_2") (pintype "passive"))
      (node (ref "L17") (pin "2") (pinfunction "2_2") (pintype "passive"))
      (node (ref "X5") (pin "1") (pinfunction "Sig_1") (pintype "passive"))
    )
    (net (code "64") (name "Net-(Z3-OUT)") (class "Default")
      (node (ref "C69") (pin "1") (pinfunction "1_1") (pintype "passive"))
      (node (ref "Z3") (pin "3") (pinfunction "OUT_3") (pintype "passive"))
    )
    (net (code "65") (name "Net-(Z3-VCC)") (class "Default")
      (node (ref "C51") (pin "2") (pinfunction "2_2") (pintype "passive"))
      (node (ref "L10") (pin "1") (pinfunction "1_1") (pintype "passive"))
      (node (ref "Z3") (pin "4") (pinfunction "VCC_4") (pintype "passive"))
    )
    (net (code "66") (name "SYS_V") (class "Default")
      (node (ref "U1") (pin "55") (pinfunction "VBAT_55") (pintype "passive"))
      (node (ref "U1") (pin "56") (pinfunction "VBAT_56") (pintype "passive"))
    )
    (net (code "67") (name "unconnected-(U1-BT_12S_DO-Pad15)") (class "Default")
      (node (ref "U1") (pin "15") (pinfunction "BT_12S_DO_15") (pintype "bidirectional"))
    )
    (net (code "68") (name "unconnected-(U1-BT_12S_WS-Pad17)") (class "Default")
      (node (ref "U1") (pin "17") (pinfunction "BT_12S_WS_17") (pintype "bidirectional"))
    )
    (net (code "69") (name "unconnected-(U1-BT_125_CLK-Pad16)") (class "Default")
      (node (ref "U1") (pin "16") (pinfunction "BT_125_CLK_16") (pintype "bidirectional"))
    )
    (net (code "70") (name "unconnected-(U1-BT_DEV_WAKE-Pad22)") (class "Default")
      (node (ref "U1") (pin "22") (pinfunction "BT_DEV_WAKE_22") (pintype "passive"))
    )
    (net (code "71") (name "unconnected-(U1-BT_PCM_CLK-Pad19)") (class "Default")
      (node (ref "U1") (pin "19") (pinfunction "BT_PCM_CLK_19") (pintype "bidirectional"))
    )
    (net (code "72") (name "unconnected-(U1-BT_PCM_IN-Pad21)") (class "Default")
      (node (ref "U1") (pin "21") (pinfunction "BT_PCM_IN_21") (pintype "bidirectional"))
    )
    (net (code "73") (name "unconnected-(U1-BT_PCM_OUT-Pad20)") (class "Default")
      (node (ref "U1") (pin "20") (pinfunction "BT_PCM_OUT_20") (pintype "bidirectional"))
    )
    (net (code "74") (name "unconnected-(U1-BT_PCM_SYNC-Pad18)") (class "Default")
      (node (ref "U1") (pin "18") (pinfunction "BT_PCM_SYNC_18") (pintype "bidirectional"))
    )
    (net (code "75") (name "unconnected-(U1-GPIO_0-Pad52)") (class "Default")
      (node (ref "U1") (pin "52") (pinfunction "GPIO_0_52") (pintype "passive"))
    )
    (net (code "76") (name "unconnected-(U1-GPIO_1-Pad53)") (class "Default")
      (node (ref "U1") (pin "53") (pinfunction "GPIO_1_53") (pintype "bidirectional"))
    )
    (net (code "77") (name "unconnected-(U1-NFC_CTS-Pad31)") (class "Default")
      (node (ref "U1") (pin "31") (pinfunction "NFC_CTS_31") (pintype "passive"))
    )
    (net (code "78") (name "unconnected-(U1-NFC_GPIO1-Pad37)") (class "Default")
      (node (ref "U1") (pin "37") (pinfunction "NFC_GPIO1_37") (pintype "bidirectional"))
    )
    (net (code "79") (name "unconnected-(U1-NFC_REG_PU-Pad14)") (class "Default")
      (node (ref "U1") (pin "14") (pinfunction "NFC_REG_PU_14") (pintype "passive"))
    )
    (net (code "80") (name "unconnected-(U1-NFC_RTS-Pad30)") (class "Default")
      (node (ref "U1") (pin "30") (pinfunction "NFC_RTS_30") (pintype "passive"))
    )
    (net (code "81") (name "unconnected-(U1-NFC_SCL-Pad35)") (class "Default")
      (node (ref "U1") (pin "35") (pinfunction "NFC_SCL_35") (pintype "passive"))
    )
    (net (code "82") (name "unconnected-(U1-NFC_SDA-Pad34)") (class "Default")
      (node (ref "U1") (pin "34") (pinfunction "NFC_SDA_34") (pintype "bidirectional"))
    )
    (net (code "83") (name "unconnected-(U1-NFC_SPI_INT-Pad36)") (class "Default")
      (node (ref "U1") (pin "36") (pinfunction "NFC_SPI_INT_36") (pintype "bidirectional"))
    )
    (net (code "84") (name "unconnected-(U1-NFC_SWPIO_0-Pad48)") (class "Default")
      (node (ref "U1") (pin "48") (pinfunction "NFC_SWPIO_0_48") (pintype "bidirectional"))
    )
    (net (code "85") (name "unconnected-(U1-NFC_TX1-Pad33)") (class "Default")
      (node (ref "U1") (pin "33") (pinfunction "NFC_TX1_33") (pintype "bidirectional"))
    )
    (net (code "86") (name "unconnected-(U1-NFC_TX2-Pad32)") (class "Default")
      (node (ref "U1") (pin "32") (pinfunction "NFC_TX2_32") (pintype "bidirectional"))
    )
    (net (code "87") (name "unconnected-(U1-NFC_URX-Pad45)") (class "Default")
      (node (ref "U1") (pin "45") (pinfunction "NFC_URX_45") (pintype "passive"))
    )
    (net (code "88") (name "unconnected-(U1-NFC_UTX-Pad46)") (class "Default")
      (node (ref "U1") (pin "46") (pinfunction "NFC_UTX_46") (pintype "passive"))
    )
    (net (code "89") (name "unconnected-(U1-NFC_VDDSWPIN_0-Pad28)") (class "Default")
      (node (ref "U1") (pin "28") (pinfunction "NFC_VDDSWPIN_0_28") (pintype "passive"))
    )
    (net (code "90") (name "unconnected-(U1-NFC_VDDSWP_0-Pad29)") (class "Default")
      (node (ref "U1") (pin "29") (pinfunction "NFC_VDDSWP_0_29") (pintype "passive"))
    )
    (net (code "91") (name "unconnected-(U1-RF_IN_2G-Pad6)") (class "Default")
      (node (ref "U1") (pin "6") (pinfunction "RF_IN_2G_6") (pintype "passive"))
    )
    (net (code "92") (name "unconnected-(U1-RF_IN_5G-Pad1)") (class "Default")
      (node (ref "U1") (pin "1") (pinfunction "RF_IN_5G_1") (pintype "passive"))
    )
    (net (code "93") (name "unconnected-(U1-RF_SW4-Pad11)") (class "Default")
      (node (ref "U1") (pin "11") (pinfunction "RF_SW4_11") (pintype "passive"))
    )
    (net (code "94") (name "unconnected-(U1-WRF_GPIO_OUT-Pad8)") (class "Default")
      (node (ref "U1") (pin "8") (pinfunction "WRF_GPIO_OUT_8") (pintype "passive"))
    )
    (net (code "95") (name "unconnected-(U16-XTB-Pad4)") (class "Default")
      (node (ref "U16") (pin "4") (pinfunction "XTB_4") (pintype "passive"))
    )
  )
)
